# SparkFun_6DoF_ISM330DHCX_Micro.net
KiCad netlist of a schematic drawn in EAGLE
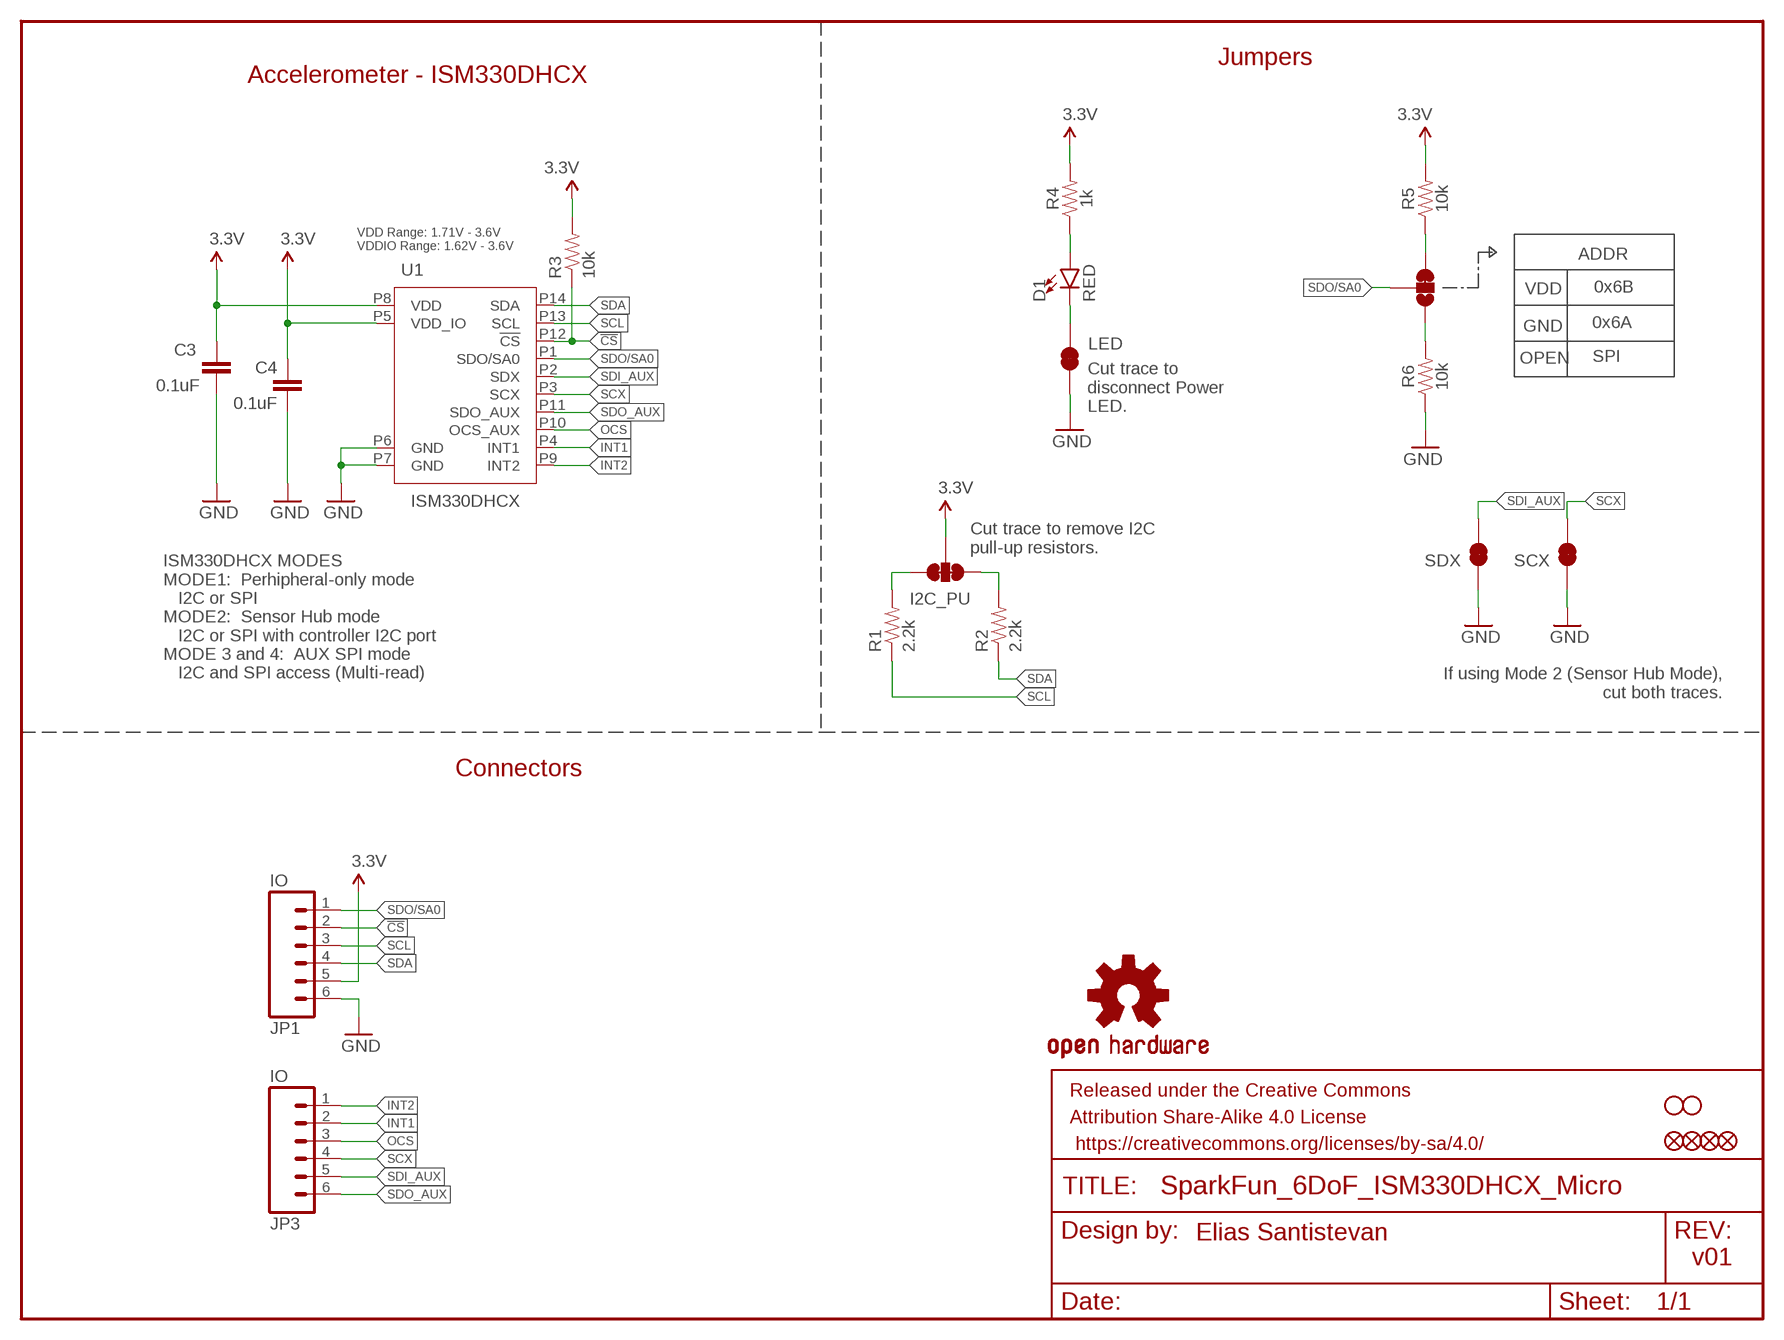
[diagram p0: schematic, sheet 1]

(export (version "E")
  (design (tool "Eeschema 10.0.6"))
  (components
    (comp (ref "ADDR")
      (value "JUMPER-SMT_3_1-NC_TRACE_SILK")
      (footprint "eagle-import:SMT-JUMPER_3_1-NC_TRACE_SILK")
      (libsource (lib "eagle-import") (part "JUMPER-SMT_3_1-NC_TRACE_SILK"))
    )
    (comp (ref "C3")
      (value "0.1uF")
      (footprint "eagle-import:0402-TIGHT")
      (libsource (lib "eagle-import") (part "0.1UF-0402T-6.3V-10%-X7R"))
    )
    (comp (ref "C4")
      (value "0.1uF")
      (footprint "eagle-import:0402-TIGHT")
      (libsource (lib "eagle-import") (part "0.1UF-0402T-6.3V-10%-X7R"))
    )
    (comp (ref "D1")
      (value "RED")
      (footprint "eagle-import:LED-0603")
      (libsource (lib "eagle-import") (part "LED-RED0603"))
    )
    (comp (ref "FD1")
      (value "FIDUCIALUFIDUCIAL")
      (footprint "eagle-import:FIDUCIAL-MICRO")
      (libsource (lib "eagle-import") (part "FIDUCIALUFIDUCIAL"))
    )
    (comp (ref "FD2")
      (value "FIDUCIALUFIDUCIAL")
      (footprint "eagle-import:FIDUCIAL-MICRO")
      (libsource (lib "eagle-import") (part "FIDUCIALUFIDUCIAL"))
    )
    (comp (ref "FID1")
      (value "FIDUCIALUFIDUCIAL")
      (footprint "eagle-import:FIDUCIAL-MICRO")
      (libsource (lib "eagle-import") (part "FIDUCIALUFIDUCIAL"))
    )
    (comp (ref "FID2")
      (value "FIDUCIALUFIDUCIAL")
      (footprint "eagle-import:FIDUCIAL-MICRO")
      (libsource (lib "eagle-import") (part "FIDUCIALUFIDUCIAL"))
    )
    (comp (ref "FRAME1")
      (value "FRAME-LETTER")
      (footprint "eagle-import:CREATIVE_COMMONS")
      (fields (field (name "DESIGNER") "Elias Santistevan"))
      (libsource (lib "eagle-import") (part "FRAME-LETTER"))
    )
    (comp (ref "I2C_PU")
      (value "S_MODE")
      (footprint "eagle-import:SMT-JUMPER_3_2-NC_TRACE_SILK")
      (libsource (lib "eagle-import") (part "JUMPER-SMT_3_2-NC_TRACE_SILK"))
    )
    (comp (ref "JP1")
      (value "IO")
      (footprint "eagle-import:1X06_NO_SILK")
      (libsource (lib "eagle-import") (part "CONN_06NO_SILK_NO_POP"))
    )
    (comp (ref "JP3")
      (value "IO")
      (footprint "eagle-import:1X06_NO_SILK")
      (libsource (lib "eagle-import") (part "CONN_06NO_SILK_NO_POP"))
    )
    (comp (ref "LED")
      (value "JUMPER-SMT_2_NC_TRACE_SILK")
      (footprint "eagle-import:SMT-JUMPER_2_NC_TRACE_SILK")
      (libsource (lib "eagle-import") (part "JUMPER-SMT_2_NC_TRACE_SILK"))
    )
    (comp (ref "LOGO2")
      (value "OSHW-LOGOMINI")
      (footprint "eagle-import:OSHW-LOGO-MINI")
      (libsource (lib "eagle-import") (part "OSHW-LOGOMINI"))
    )
    (comp (ref "R1")
      (value "2.2k")
      (footprint "eagle-import:0402-TIGHT")
      (libsource (lib "eagle-import") (part "2.2KOHM-0402T-1/16W-1%"))
    )
    (comp (ref "R2")
      (value "2.2k")
      (footprint "eagle-import:0402-TIGHT")
      (libsource (lib "eagle-import") (part "2.2KOHM-0402T-1/16W-1%"))
    )
    (comp (ref "R3")
      (value "10k")
      (footprint "eagle-import:0402-TIGHT")
      (libsource (lib "eagle-import") (part "10KOHM-0402T-1/16W-1%"))
    )
    (comp (ref "R4")
      (value "1k")
      (footprint "eagle-import:0402-TIGHT")
      (libsource (lib "eagle-import") (part "1KOHM-0402T-1/16W-1%"))
    )
    (comp (ref "R5")
      (value "10k")
      (footprint "eagle-import:0402-TIGHT")
      (libsource (lib "eagle-import") (part "10KOHM-0402T-1/16W-1%"))
    )
    (comp (ref "R6")
      (value "10k")
      (footprint "eagle-import:0402-TIGHT")
      (libsource (lib "eagle-import") (part "10KOHM-0402T-1/16W-1%"))
    )
    (comp (ref "SCX")
      (value "JUMPER-SMT_2_NC_TRACE_SILK")
      (footprint "eagle-import:SMT-JUMPER_2_NC_TRACE_SILK")
      (libsource (lib "eagle-import") (part "JUMPER-SMT_2_NC_TRACE_SILK"))
    )
    (comp (ref "SDX")
      (value "JUMPER-SMT_2_NC_TRACE_SILK")
      (footprint "eagle-import:SMT-JUMPER_2_NC_TRACE_SILK")
      (libsource (lib "eagle-import") (part "JUMPER-SMT_2_NC_TRACE_SILK"))
    )
    (comp (ref "STANDOFF1")
      (value "STAND-OFFTIGHT")
      (footprint "eagle-import:STAND-OFF-TIGHT")
      (libsource (lib "eagle-import") (part "STAND-OFFTIGHT"))
    )
    (comp (ref "STANDOFF2")
      (value "STAND-OFFTIGHT")
      (footprint "eagle-import:STAND-OFF-TIGHT")
      (libsource (lib "eagle-import") (part "STAND-OFFTIGHT"))
    )
    (comp (ref "U1")
      (value "ISM330DHCX")
      (footprint "eagle-import:LGA-14L")
      (libsource (lib "eagle-import") (part "ISM330DHCX"))
    )
  )
  (nets
    (net (code "1") (name "/~{CS}") (class "Default")
      (node (ref "JP1") (pin "2") (pinfunction "2_2") (pintype "passive"))
      (node (ref "R3") (pin "1") (pinfunction "1_1") (pintype "passive"))
      (node (ref "U1") (pin "P12") (pinfunction "~{CS}_P12") (pintype "bidirectional"))
    )
    (net (code "2") (name "3.3V") (class "Default")
      (node (ref "C3") (pin "1") (pinfunction "1_1") (pintype "passive"))
      (node (ref "C4") (pin "1") (pinfunction "1_1") (pintype "passive"))
      (node (ref "I2C_PU") (pin "2") (pinfunction "2_2") (pintype "passive"))
      (node (ref "JP1") (pin "5") (pinfunction "5_5") (pintype "passive"))
      (node (ref "R3") (pin "2") (pinfunction "2_2") (pintype "passive"))
      (node (ref "R4") (pin "2") (pinfunction "2_2") (pintype "passive"))
      (node (ref "R5") (pin "2") (pinfunction "2_2") (pintype "passive"))
      (node (ref "U1") (pin "P5") (pinfunction "VDD_IO_P5") (pintype "power_in"))
      (node (ref "U1") (pin "P8") (pinfunction "VDD_P8") (pintype "power_in"))
    )
    (net (code "3") (name "GND") (class "Default")
      (node (ref "C3") (pin "2") (pinfunction "2_2") (pintype "passive"))
      (node (ref "C4") (pin "2") (pinfunction "2_2") (pintype "passive"))
      (node (ref "JP1") (pin "6") (pinfunction "6_6") (pintype "passive"))
      (node (ref "LED") (pin "1") (pinfunction "1_1") (pintype "passive"))
      (node (ref "R6") (pin "1") (pinfunction "1_1") (pintype "passive"))
      (node (ref "SCX") (pin "1") (pinfunction "1_1") (pintype "passive"))
      (node (ref "SDX") (pin "1") (pinfunction "1_1") (pintype "passive"))
      (node (ref "U1") (pin "P6") (pinfunction "GND_P6") (pintype "power_in"))
      (node (ref "U1") (pin "P7") (pinfunction "GND_P7") (pintype "power_in"))
    )
    (net (code "4") (name "INT1") (class "Default")
      (node (ref "JP3") (pin "2") (pinfunction "2_2") (pintype "passive"))
      (node (ref "U1") (pin "P4") (pinfunction "INT1_P4") (pintype "bidirectional"))
    )
    (net (code "5") (name "INT2") (class "Default")
      (node (ref "JP3") (pin "1") (pinfunction "1_1") (pintype "passive"))
      (node (ref "U1") (pin "P9") (pinfunction "INT2_P9") (pintype "bidirectional"))
    )
    (net (code "6") (name "Net-(ADDR-Pad1)") (class "Default")
      (node (ref "ADDR") (pin "1") (pinfunction "1_1") (pintype "passive"))
      (node (ref "R6") (pin "2") (pinfunction "2_2") (pintype "passive"))
    )
    (net (code "7") (name "Net-(ADDR-Pad3)") (class "Default")
      (node (ref "ADDR") (pin "3") (pinfunction "3_3") (pintype "passive"))
      (node (ref "R5") (pin "1") (pinfunction "1_1") (pintype "passive"))
    )
    (net (code "8") (name "Net-(D1-PadA)") (class "Default")
      (node (ref "D1") (pin "A") (pinfunction "A_A") (pintype "passive"))
      (node (ref "R4") (pin "1") (pinfunction "1_1") (pintype "passive"))
    )
    (net (code "9") (name "Net-(D1-PadC)") (class "Default")
      (node (ref "D1") (pin "C") (pinfunction "C_C") (pintype "passive"))
      (node (ref "LED") (pin "2") (pinfunction "2_2") (pintype "passive"))
    )
    (net (code "10") (name "Net-(I2C_PU-Pad1)") (class "Default")
      (node (ref "I2C_PU") (pin "1") (pinfunction "1_1") (pintype "passive"))
      (node (ref "R1") (pin "2") (pinfunction "2_2") (pintype "passive"))
    )
    (net (code "11") (name "Net-(I2C_PU-Pad3)") (class "Default")
      (node (ref "I2C_PU") (pin "3") (pinfunction "3_3") (pintype "passive"))
      (node (ref "R2") (pin "2") (pinfunction "2_2") (pintype "passive"))
    )
    (net (code "12") (name "OCS") (class "Default")
      (node (ref "JP3") (pin "3") (pinfunction "3_3") (pintype "passive"))
      (node (ref "U1") (pin "P10") (pinfunction "OCS_AUX_P10") (pintype "bidirectional"))
    )
    (net (code "13") (name "SCL") (class "Default")
      (node (ref "JP1") (pin "3") (pinfunction "3_3") (pintype "passive"))
      (node (ref "R1") (pin "1") (pinfunction "1_1") (pintype "passive"))
      (node (ref "U1") (pin "P13") (pinfunction "SCL_P13") (pintype "bidirectional"))
    )
    (net (code "14") (name "SCX") (class "Default")
      (node (ref "JP3") (pin "4") (pinfunction "4_4") (pintype "passive"))
      (node (ref "SCX") (pin "2") (pinfunction "2_2") (pintype "passive"))
      (node (ref "U1") (pin "P3") (pinfunction "SCX_P3") (pintype "bidirectional"))
    )
    (net (code "15") (name "SDA") (class "Default")
      (node (ref "JP1") (pin "4") (pinfunction "4_4") (pintype "passive"))
      (node (ref "R2") (pin "1") (pinfunction "1_1") (pintype "passive"))
      (node (ref "U1") (pin "P14") (pinfunction "SDA_P14") (pintype "bidirectional"))
    )
    (net (code "16") (name "SDI_AUX") (class "Default")
      (node (ref "JP3") (pin "5") (pinfunction "5_5") (pintype "passive"))
      (node (ref "SDX") (pin "2") (pinfunction "2_2") (pintype "passive"))
      (node (ref "U1") (pin "P2") (pinfunction "SDX_P2") (pintype "bidirectional"))
    )
    (net (code "17") (name "SDO_AUX") (class "Default")
      (node (ref "JP3") (pin "6") (pinfunction "6_6") (pintype "passive"))
      (node (ref "U1") (pin "P11") (pinfunction "SDO_AUX_P11") (pintype "bidirectional"))
    )
    (net (code "18") (name "SDO{slash}SA0") (class "Default")
      (node (ref "ADDR") (pin "2") (pinfunction "2_2") (pintype "passive"))
      (node (ref "JP1") (pin "1") (pinfunction "1_1") (pintype "passive"))
      (node (ref "U1") (pin "P1") (pinfunction "SDO/SA0_P1") (pintype "bidirectional"))
    )
  )
)
